# Power.net
KiCad netlist of a schematic drawn in Altium Designer
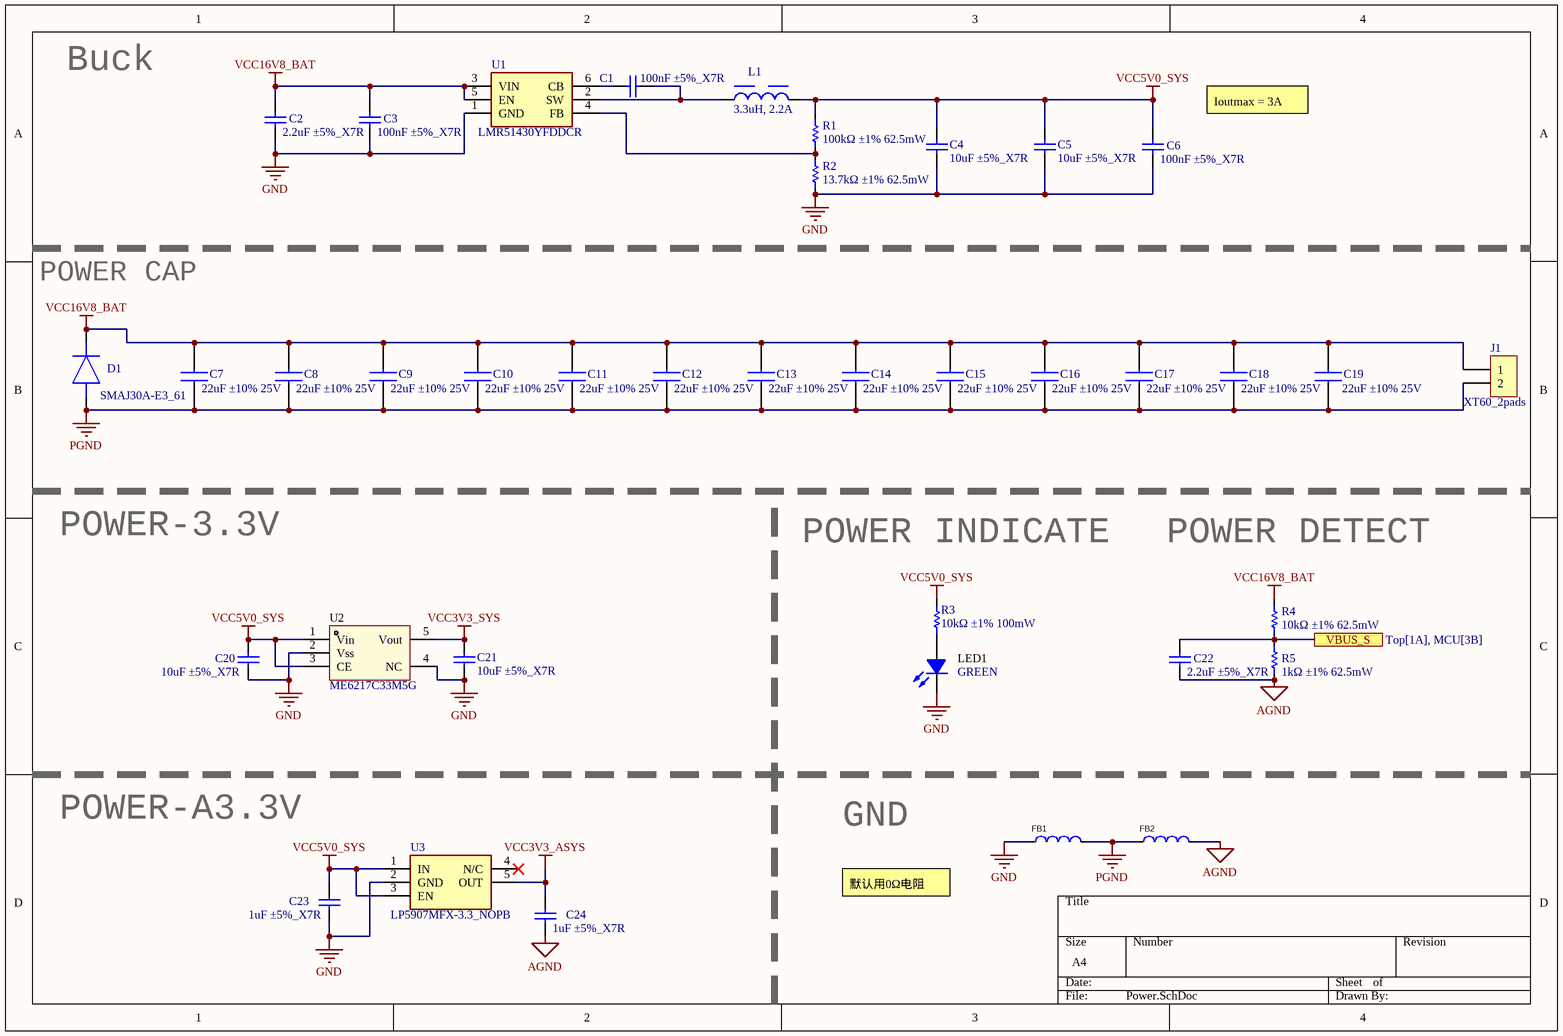
[diagram p0: Power.SchDoc]

(export (version "E")
  (design (tool "Eeschema 10.0.6"))
  (components
    (comp (ref "C1")
      (value "100nF ±5%_X7R")
      (footprint "WCAP-CSGP_0402_L1W0.5H0.5")
      (description "Capacitor")
      (fields (field (name "PUBLISHER") "Altium Limited"))
      (libsource (lib "Component") (part "Cap"))
    )
    (comp (ref "C2")
      (value "2.2uF ±5%_X7R")
      (footprint "WCAP-CSGP_0603_L1.6W0.8H0.8_Reflow")
      (description "Capacitor")
      (fields (field (name "PUBLISHER") "Altium Limited"))
      (libsource (lib "Component") (part "Cap"))
    )
    (comp (ref "C3")
      (value "100nF ±5%_X7R")
      (footprint "WCAP-CSGP_0402_L1W0.5H0.5")
      (description "Capacitor")
      (fields (field (name "PUBLISHER") "Altium Limited"))
      (libsource (lib "Component") (part "Cap"))
    )
    (comp (ref "C4")
      (value "10uF ±5%_X7R")
      (footprint "WCAP-CSGP_0603_L1.6W0.8H0.8_Reflow")
      (description "Capacitor")
      (fields (field (name "PUBLISHER") "Altium Limited"))
      (libsource (lib "Component") (part "Cap"))
    )
    (comp (ref "C5")
      (value "10uF ±5%_X7R")
      (footprint "WCAP-CSGP_0603_L1.6W0.8H0.8_Reflow")
      (description "Capacitor")
      (fields (field (name "PUBLISHER") "Altium Limited"))
      (libsource (lib "Component") (part "Cap"))
    )
    (comp (ref "C6")
      (value "100nF ±5%_X7R")
      (footprint "WCAP-CSGP_0402_L1W0.5H0.5")
      (description "Capacitor")
      (fields (field (name "PUBLISHER") "Altium Limited"))
      (libsource (lib "Component") (part "Cap"))
    )
    (comp (ref "C7")
      (value "22uF ±10% 25V")
      (footprint "SamacSys:CAPC3225X270N")
      (description "Capacitor")
      (fields
        (field (name "MANUFACTURER_PART_NUMBER") "CL32A226KAJNNNE")
        (field (name "MOUSER PART NUMBER") "187-CL32A226KAJNNNE")
      )
      (libsource (lib "*") (part "CL32A226KAJNNNE"))
    )
    (comp (ref "C8")
      (value "22uF ±10% 25V")
      (footprint "SamacSys:CAPC3225X270N")
      (description "Capacitor")
      (fields
        (field (name "MANUFACTURER_PART_NUMBER") "CL32A226KAJNNNE")
        (field (name "MOUSER PART NUMBER") "187-CL32A226KAJNNNE")
      )
      (libsource (lib "*") (part "CL32A226KAJNNNE"))
    )
    (comp (ref "C9")
      (value "22uF ±10% 25V")
      (footprint "SamacSys:CAPC3225X270N")
      (description "Capacitor")
      (fields
        (field (name "MANUFACTURER_PART_NUMBER") "CL32A226KAJNNNE")
        (field (name "MOUSER PART NUMBER") "187-CL32A226KAJNNNE")
      )
      (libsource (lib "*") (part "CL32A226KAJNNNE"))
    )
    (comp (ref "C10")
      (value "22uF ±10% 25V")
      (footprint "SamacSys:CAPC3225X270N")
      (description "Capacitor")
      (fields
        (field (name "MANUFACTURER_PART_NUMBER") "CL32A226KAJNNNE")
        (field (name "MOUSER PART NUMBER") "187-CL32A226KAJNNNE")
      )
      (libsource (lib "*") (part "CL32A226KAJNNNE"))
    )
    (comp (ref "C11")
      (value "22uF ±10% 25V")
      (footprint "SamacSys:CAPC3225X270N")
      (description "Capacitor")
      (fields
        (field (name "MANUFACTURER_PART_NUMBER") "CL32A226KAJNNNE")
        (field (name "MOUSER PART NUMBER") "187-CL32A226KAJNNNE")
      )
      (libsource (lib "*") (part "CL32A226KAJNNNE"))
    )
    (comp (ref "C12")
      (value "22uF ±10% 25V")
      (footprint "SamacSys:CAPC3225X270N")
      (description "Capacitor")
      (fields
        (field (name "MANUFACTURER_PART_NUMBER") "CL32A226KAJNNNE")
        (field (name "MOUSER PART NUMBER") "187-CL32A226KAJNNNE")
      )
      (libsource (lib "*") (part "CL32A226KAJNNNE"))
    )
    (comp (ref "C13")
      (value "22uF ±10% 25V")
      (footprint "SamacSys:CAPC3225X270N")
      (description "Capacitor")
      (fields
        (field (name "MANUFACTURER_PART_NUMBER") "CL32A226KAJNNNE")
        (field (name "MOUSER PART NUMBER") "187-CL32A226KAJNNNE")
      )
      (libsource (lib "*") (part "CL32A226KAJNNNE"))
    )
    (comp (ref "C14")
      (value "22uF ±10% 25V")
      (footprint "CAPC3225X270N")
      (description "Capacitor")
      (fields
        (field (name "MANUFACTURER_PART_NUMBER") "CL32A226KAJNNNE")
        (field (name "MOUSER PART NUMBER") "187-CL32A226KAJNNNE")
      )
      (libsource (lib "*") (part "CL32A226KAJNNNE"))
    )
    (comp (ref "C15")
      (value "22uF ±10% 25V")
      (footprint "CAPC3225X270N")
      (description "Capacitor")
      (fields
        (field (name "MANUFACTURER_PART_NUMBER") "CL32A226KAJNNNE")
        (field (name "MOUSER PART NUMBER") "187-CL32A226KAJNNNE")
      )
      (libsource (lib "*") (part "CL32A226KAJNNNE"))
    )
    (comp (ref "C16")
      (value "22uF ±10% 25V")
      (footprint "CAPC3225X270N")
      (description "Capacitor")
      (fields
        (field (name "MANUFACTURER_PART_NUMBER") "CL32A226KAJNNNE")
        (field (name "MOUSER PART NUMBER") "187-CL32A226KAJNNNE")
      )
      (libsource (lib "*") (part "CL32A226KAJNNNE"))
    )
    (comp (ref "C17")
      (value "22uF ±10% 25V")
      (footprint "CAPC3225X270N")
      (description "Capacitor")
      (fields
        (field (name "MANUFACTURER_PART_NUMBER") "CL32A226KAJNNNE")
        (field (name "MOUSER PART NUMBER") "187-CL32A226KAJNNNE")
      )
      (libsource (lib "*") (part "CL32A226KAJNNNE"))
    )
    (comp (ref "C18")
      (value "22uF ±10% 25V")
      (footprint "CAPC3225X270N")
      (description "Capacitor")
      (fields
        (field (name "MANUFACTURER_PART_NUMBER") "CL32A226KAJNNNE")
        (field (name "MOUSER PART NUMBER") "187-CL32A226KAJNNNE")
      )
      (libsource (lib "*") (part "CL32A226KAJNNNE"))
    )
    (comp (ref "C19")
      (value "22uF ±10% 25V")
      (footprint "CAPC3225X270N")
      (description "Capacitor")
      (fields
        (field (name "MANUFACTURER_PART_NUMBER") "CL32A226KAJNNNE")
        (field (name "MOUSER PART NUMBER") "187-CL32A226KAJNNNE")
      )
      (libsource (lib "*") (part "CL32A226KAJNNNE"))
    )
    (comp (ref "C20")
      (value "10uF ±5%_X7R")
      (footprint "WCAP-CSGP_0603_L1.6W0.8H0.8_Reflow")
      (description "Capacitor")
      (fields (field (name "PUBLISHER") "Altium Limited"))
      (libsource (lib "Component") (part "Cap"))
    )
    (comp (ref "C21")
      (value "10uF ±5%_X7R")
      (footprint "WCAP-CSGP_0603_L1.6W0.8H0.8_Reflow")
      (description "Capacitor")
      (fields (field (name "PUBLISHER") "Altium Limited"))
      (libsource (lib "Component") (part "Cap"))
    )
    (comp (ref "C22")
      (value "2.2uF ±5%_X7R")
      (footprint "WCAP-CSGP_0402_L1W0.5H0.5")
      (description "Capacitor")
      (fields (field (name "PUBLISHER") "Altium Limited"))
      (libsource (lib "Component") (part "Cap"))
    )
    (comp (ref "C23")
      (value "1uF ±5%_X7R")
      (footprint "WCAP-CSGP_0603_L1.6W0.8H0.8_Reflow")
      (description "Capacitor")
      (fields (field (name "PUBLISHER") "Altium Limited"))
      (libsource (lib "Component") (part "Cap"))
    )
    (comp (ref "C24")
      (value "1uF ±5%_X7R")
      (footprint "WCAP-CSGP_0603_L1.6W0.8H0.8_Reflow")
      (description "Capacitor")
      (fields (field (name "PUBLISHER") "Altium Limited"))
      (libsource (lib "Component") (part "Cap"))
    )
    (comp (ref "D1")
      (value "SMAJ30A-E3_61")
      (footprint "SamacSys:DIOM5127X229N")
      (description "Diode")
      (fields
        (field (name "MANUFACTURER_PART_NUMBER") "SMAJ30A-E3/61")
        (field (name "MOUSER PART NUMBER") "625-SMAJ30A-E3")
      )
      (libsource (lib "*") (part "SMAJ30A-E3_61"))
    )
    (comp (ref "FB1")
      (value "?Ω@100MHz")
      (footprint "BEADC1608X75N")
      (description "MPZ1608S601ATA00")
      (fields (field (name "MANUFACTURER") "FH(风华)") (field (name "MANUFACTURER PART") "CBW321609U601T"))
      (libsource (lib "Component") (part "Ferrite Bead"))
    )
    (comp (ref "FB2")
      (value "?Ω@100MHz")
      (footprint "BEADC1608X75N")
      (description "MPZ1608S601ATA00")
      (fields (field (name "MANUFACTURER") "FH(风华)") (field (name "MANUFACTURER PART") "CBW321609U601T"))
      (libsource (lib "Component") (part "Ferrite Bead"))
    )
    (comp (ref "J1")
      (value "XT60_2pads")
      (footprint "XT60_2pads")
      (libsource (lib "Connectivity_Plugs") (part "XT60_2pads"))
    )
    (comp (ref "L1")
      (value "3.3uH, 2.2A")
      (footprint "WE-MAPI_3020")
      (description "WE-MAPI, size 3020, 3.3uH, 2.2A, 114mOhm")
      (fields
        (field (name "MANUFACTURER PART NUMBER") "74438336033")
        (field (name "MANUFACTURER") "Wurth Elektronik")
      )
      (libsource (lib "WE-MAPI (rev24b)") (part "74438336033"))
    )
    (comp (ref "LED1")
      (value "GREEN")
      (footprint "LED0603-RD")
      (fields
        (field (name "MANUFACTURER") "EVERLIGHT(亿光)")
        (field (name "MANUFACTURER PART") "17-21SURC/S530-A2/TR8")
      )
      (libsource (lib "Component") (part "LED"))
    )
    (comp (ref "R1")
      (value "100kΩ ±1% 62.5mW")
      (footprint "WRIS-KSKE_0402")
      (description "Resistor")
      (fields (field (name "PUBLISHER") "Altium Limited"))
      (libsource (lib "Component") (part "Res"))
    )
    (comp (ref "R2")
      (value "13.7kΩ ±1% 62.5mW")
      (footprint "WRIS-KSKE_0402")
      (description "Resistor")
      (fields (field (name "PUBLISHER") "Altium Limited"))
      (libsource (lib "Component") (part "Res"))
    )
    (comp (ref "R3")
      (value "10kΩ ±1% 100mW")
      (footprint "R0603")
      (description "Resistor")
      (fields (field (name "PUBLISHER") "Altium Limited"))
      (libsource (lib "Component") (part "Res"))
    )
    (comp (ref "R4")
      (value "10kΩ ±1% 62.5mW")
      (footprint "WRIS-KSKE_0402")
      (description "Resistor")
      (fields (field (name "PUBLISHER") "Altium Limited"))
      (libsource (lib "Component") (part "Res"))
    )
    (comp (ref "R5")
      (value "1kΩ ±1% 62.5mW")
      (footprint "WRIS-KSKE_0402")
      (description "Resistor")
      (fields (field (name "PUBLISHER") "Altium Limited"))
      (libsource (lib "Component") (part "Res"))
    )
    (comp (ref "U1")
      (value "LMR51430YFDDCR")
      (footprint "SamacSys:SOT95P280X110-6N")
      (description "Integrated Circuit")
      (fields (field (name "MOUSER PART NUMBER") "595-LMR51430YFDDCR"))
      (libsource (lib "SamacSys") (part "LMR51430YFDDCR"))
    )
    (comp (ref "U2")
      (value "ME6217C33M5G")
      (footprint "SOT-23-5_L3.0-W1.7-P0.95-LS2.8-BR")
      (fields (field (name "MANUFACTURER") "MICRONE(南京微盟)"))
      (libsource (lib "IC") (part "ME6217C33M5G"))
    )
    (comp (ref "U3")
      (value "LP5907MFX-3.3_NOPB")
      (footprint "SOT95P280X145-5N")
      (description "Integrated Circuit")
      (fields
        (field (name "MANUFACTURER_PART_NUMBER") "LP5907MFX-3.3/NOPB")
        (field (name "MOUSER PART NUMBER") "595-LP5907MFX-3.3NPB")
      )
      (libsource (lib "*") (part "LP5907MFX-3.3_NOPB"))
    )
  )
  (nets
    (net (code "1") (name "/VBUS_S") (class "Default")
      (node (ref "C22") (pin "2") (pinfunction "2_2") (pintype "passive"))
      (node (ref "R4") (pin "1") (pinfunction "1_1") (pintype "passive"))
      (node (ref "R5") (pin "2") (pinfunction "2_2") (pintype "passive"))
    )
    (net (code "2") (name "AGND") (class "Default")
      (node (ref "C22") (pin "1") (pinfunction "1_1") (pintype "passive"))
      (node (ref "C24") (pin "1") (pinfunction "1_1") (pintype "passive"))
      (node (ref "FB2") (pin "2") (pinfunction "2_2") (pintype "passive"))
      (node (ref "R5") (pin "1") (pinfunction "1_1") (pintype "passive"))
    )
    (net (code "3") (name "GND") (class "Default")
      (node (ref "C2") (pin "1") (pinfunction "1_1") (pintype "passive"))
      (node (ref "C20") (pin "1") (pinfunction "1_1") (pintype "passive"))
      (node (ref "C21") (pin "1") (pinfunction "1_1") (pintype "passive"))
      (node (ref "C23") (pin "1") (pinfunction "1_1") (pintype "passive"))
      (node (ref "C3") (pin "1") (pinfunction "1_1") (pintype "passive"))
      (node (ref "C4") (pin "1") (pinfunction "1_1") (pintype "passive"))
      (node (ref "C5") (pin "1") (pinfunction "1_1") (pintype "passive"))
      (node (ref "C6") (pin "1") (pinfunction "1_1") (pintype "passive"))
      (node (ref "FB1") (pin "1") (pinfunction "1_1") (pintype "passive"))
      (node (ref "LED1") (pin "2") (pinfunction "K_2") (pintype "passive"))
      (node (ref "R2") (pin "1") (pinfunction "1_1") (pintype "passive"))
      (node (ref "U1") (pin "1") (pinfunction "GND_1") (pintype "passive"))
      (node (ref "U2") (pin "2") (pinfunction "Vss_2") (pintype "passive"))
      (node (ref "U2") (pin "4") (pinfunction "NC_4") (pintype "passive"))
      (node (ref "U3") (pin "2") (pinfunction "GND_2") (pintype "passive"))
    )
    (net (code "4") (name "Net-(LED1-A)") (class "Default")
      (node (ref "LED1") (pin "1") (pinfunction "A_1") (pintype "passive"))
      (node (ref "R3") (pin "1") (pinfunction "1_1") (pintype "passive"))
    )
    (net (code "5") (name "Net-(U1-CB)") (class "Default")
      (node (ref "C1") (pin "2") (pinfunction "2_2") (pintype "passive"))
      (node (ref "U1") (pin "6") (pinfunction "CB_6") (pintype "passive"))
    )
    (net (code "6") (name "Net-(U1-FB)") (class "Default")
      (node (ref "R1") (pin "1") (pinfunction "1_1") (pintype "passive"))
      (node (ref "R2") (pin "2") (pinfunction "2_2") (pintype "passive"))
      (node (ref "U1") (pin "4") (pinfunction "FB_4") (pintype "passive"))
    )
    (net (code "7") (name "Net-(U1-SW)") (class "Default")
      (node (ref "C1") (pin "1") (pinfunction "1_1") (pintype "passive"))
      (node (ref "L1") (pin "1") (pinfunction "1_1") (pintype "passive"))
      (node (ref "U1") (pin "2") (pinfunction "SW_2") (pintype "passive"))
    )
    (net (code "8") (name "PGND") (class "Default")
      (node (ref "C10") (pin "1") (pinfunction "1_1") (pintype "passive"))
      (node (ref "C11") (pin "1") (pinfunction "1_1") (pintype "passive"))
      (node (ref "C12") (pin "1") (pinfunction "1_1") (pintype "passive"))
      (node (ref "C13") (pin "1") (pinfunction "1_1") (pintype "passive"))
      (node (ref "C14") (pin "1") (pinfunction "1_1") (pintype "passive"))
      (node (ref "C15") (pin "1") (pinfunction "1_1") (pintype "passive"))
      (node (ref "C16") (pin "1") (pinfunction "1_1") (pintype "passive"))
      (node (ref "C17") (pin "1") (pinfunction "1_1") (pintype "passive"))
      (node (ref "C18") (pin "1") (pinfunction "1_1") (pintype "passive"))
      (node (ref "C19") (pin "1") (pinfunction "1_1") (pintype "passive"))
      (node (ref "C7") (pin "1") (pinfunction "1_1") (pintype "passive"))
      (node (ref "C8") (pin "1") (pinfunction "1_1") (pintype "passive"))
      (node (ref "C9") (pin "1") (pinfunction "1_1") (pintype "passive"))
      (node (ref "D1") (pin "2") (pinfunction "A_2") (pintype "passive"))
      (node (ref "FB1") (pin "2") (pinfunction "2_2") (pintype "passive"))
      (node (ref "FB2") (pin "1") (pinfunction "1_1") (pintype "passive"))
      (node (ref "J1") (pin "2") (pinfunction "2_2") (pintype "passive"))
    )
    (net (code "9") (name "VCC3V3_ASYS") (class "Default")
      (node (ref "C24") (pin "2") (pinfunction "2_2") (pintype "passive"))
      (node (ref "U3") (pin "5") (pinfunction "OUT_5") (pintype "passive"))
    )
    (net (code "10") (name "VCC3V3_SYS") (class "Default")
      (node (ref "C21") (pin "2") (pinfunction "2_2") (pintype "passive"))
      (node (ref "U2") (pin "5") (pinfunction "Vout_5") (pintype "passive"))
    )
    (net (code "11") (name "VCC5V0_SYS") (class "Default")
      (node (ref "C20") (pin "2") (pinfunction "2_2") (pintype "passive"))
      (node (ref "C23") (pin "2") (pinfunction "2_2") (pintype "passive"))
      (node (ref "C4") (pin "2") (pinfunction "2_2") (pintype "passive"))
      (node (ref "C5") (pin "2") (pinfunction "2_2") (pintype "passive"))
      (node (ref "C6") (pin "2") (pinfunction "2_2") (pintype "passive"))
      (node (ref "L1") (pin "2") (pinfunction "2_2") (pintype "passive"))
      (node (ref "R1") (pin "2") (pinfunction "2_2") (pintype "passive"))
      (node (ref "R3") (pin "2") (pinfunction "2_2") (pintype "passive"))
      (node (ref "U2") (pin "1") (pinfunction "Vin_1") (pintype "passive"))
      (node (ref "U2") (pin "3") (pinfunction "CE_3") (pintype "passive"))
      (node (ref "U3") (pin "1") (pinfunction "IN_1") (pintype "passive"))
      (node (ref "U3") (pin "3") (pinfunction "EN_3") (pintype "passive"))
    )
    (net (code "12") (name "VCC16V8_BAT") (class "Default")
      (node (ref "C10") (pin "2") (pinfunction "2_2") (pintype "passive"))
      (node (ref "C11") (pin "2") (pinfunction "2_2") (pintype "passive"))
      (node (ref "C12") (pin "2") (pinfunction "2_2") (pintype "passive"))
      (node (ref "C13") (pin "2") (pinfunction "2_2") (pintype "passive"))
      (node (ref "C14") (pin "2") (pinfunction "2_2") (pintype "passive"))
      (node (ref "C15") (pin "2") (pinfunction "2_2") (pintype "passive"))
      (node (ref "C16") (pin "2") (pinfunction "2_2") (pintype "passive"))
      (node (ref "C17") (pin "2") (pinfunction "2_2") (pintype "passive"))
      (node (ref "C18") (pin "2") (pinfunction "2_2") (pintype "passive"))
      (node (ref "C19") (pin "2") (pinfunction "2_2") (pintype "passive"))
      (node (ref "C2") (pin "2") (pinfunction "2_2") (pintype "passive"))
      (node (ref "C3") (pin "2") (pinfunction "2_2") (pintype "passive"))
      (node (ref "C7") (pin "2") (pinfunction "2_2") (pintype "passive"))
      (node (ref "C8") (pin "2") (pinfunction "2_2") (pintype "passive"))
      (node (ref "C9") (pin "2") (pinfunction "2_2") (pintype "passive"))
      (node (ref "D1") (pin "1") (pinfunction "K_1") (pintype "passive"))
      (node (ref "J1") (pin "1") (pinfunction "1_1") (pintype "passive"))
      (node (ref "R4") (pin "2") (pinfunction "2_2") (pintype "passive"))
      (node (ref "U1") (pin "3") (pinfunction "VIN_3") (pintype "passive"))
      (node (ref "U1") (pin "5") (pinfunction "EN_5") (pintype "passive"))
    )
    (net (code "13") (name "unconnected-(U3-N{slash}C-Pad4)") (class "Default")
      (node (ref "U3") (pin "4") (pinfunction "N/C_4") (pintype "passive+no_connect"))
    )
  )
)
